# Moty_Light.net
KiCad netlist of a schematic drawn in EAGLE
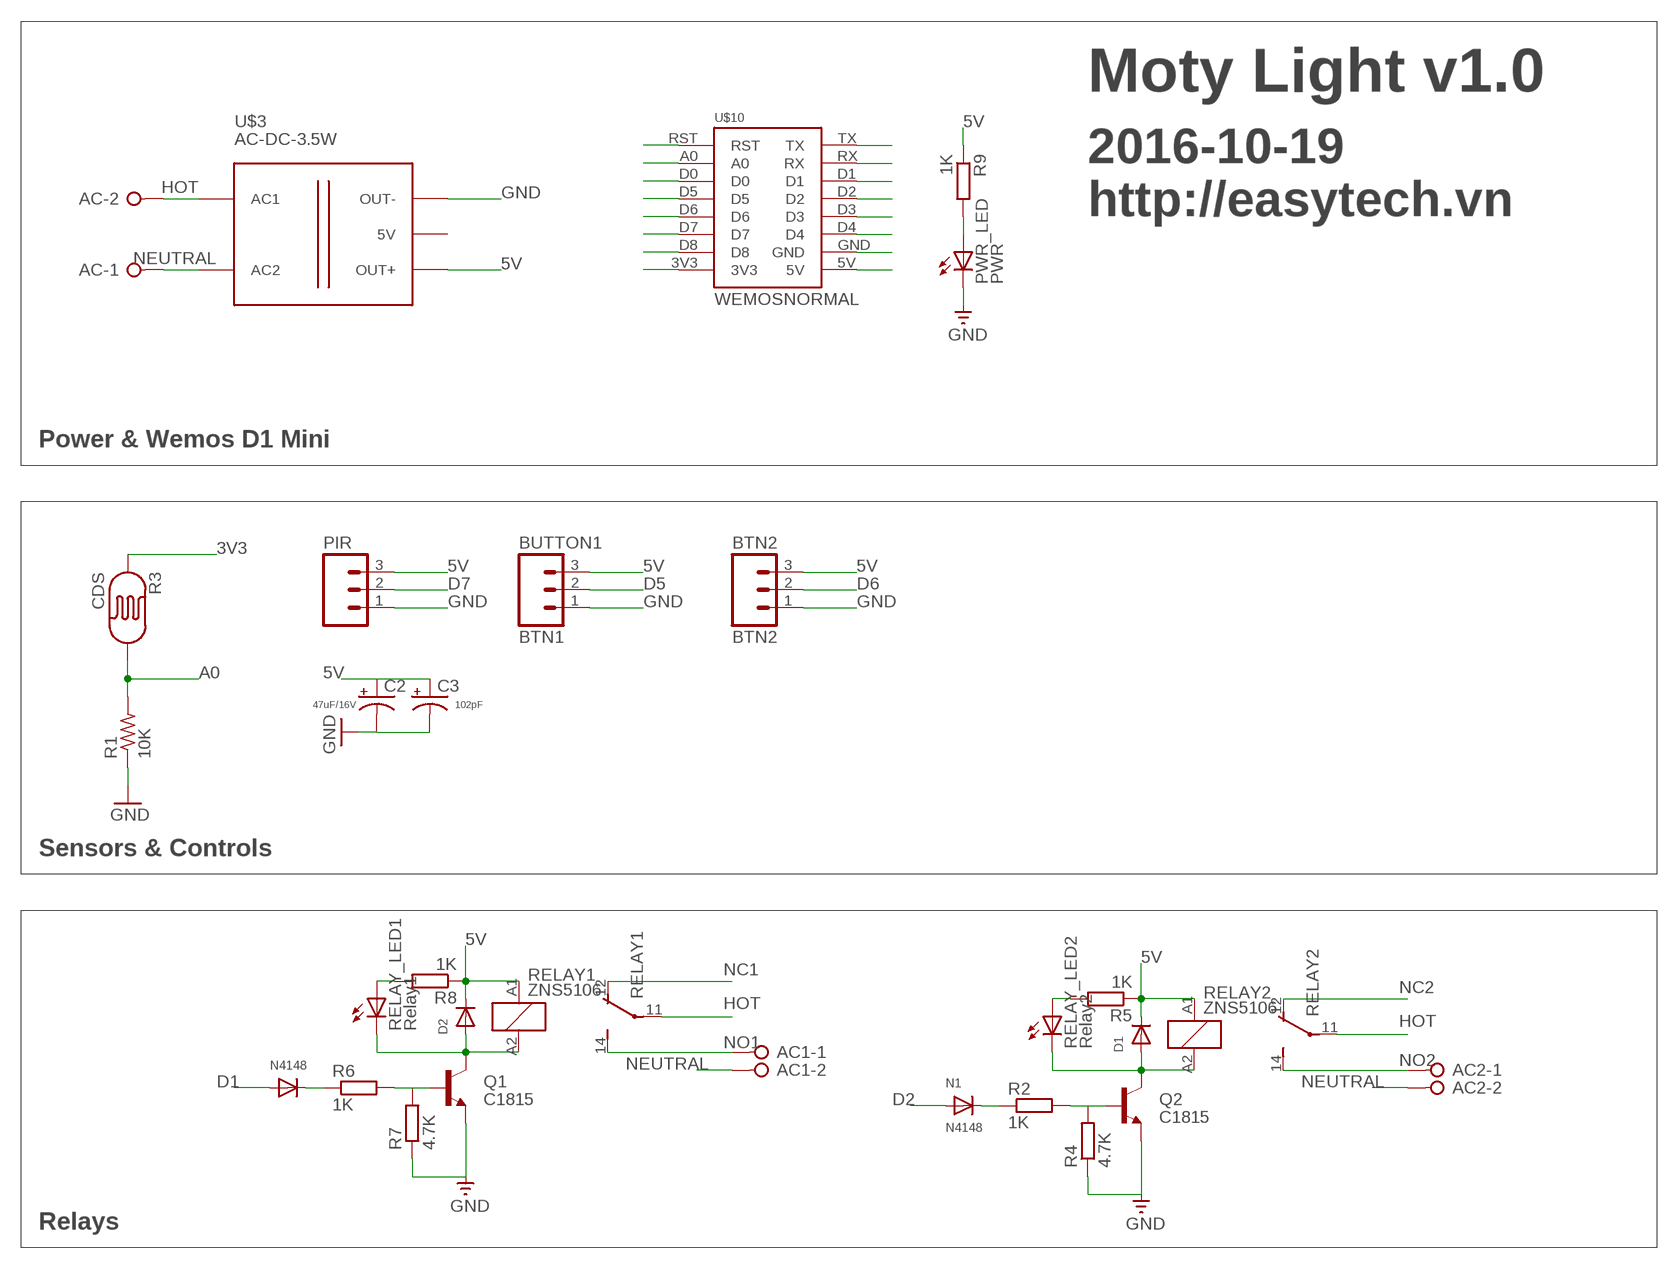
[diagram p0: schematic, sheet 1]

(export (version "E")
  (design (tool "Eeschema 10.0.6"))
  (components
    (comp (ref "AC")
      (value "W237-02P")
      (footprint "eagle-import:W237-132")
      (libsource (lib "eagle-import") (part "W237-02P"))
    )
    (comp (ref "AC1")
      (value "W237-02P")
      (footprint "eagle-import:W237-132")
      (libsource (lib "eagle-import") (part "W237-02P"))
    )
    (comp (ref "AC2")
      (value "W237-02P")
      (footprint "eagle-import:W237-132")
      (libsource (lib "eagle-import") (part "W237-02P"))
    )
    (comp (ref "BTN2")
      (value "BTN2")
      (footprint "eagle-import:1X03")
      (libsource (lib "eagle-import") (part "M03PTH"))
    )
    (comp (ref "BUTTON1")
      (value "BTN1")
      (footprint "eagle-import:1X03")
      (libsource (lib "eagle-import") (part "M03PTH"))
    )
    (comp (ref "C2")
      (value "47uF/16V")
      (footprint "eagle-import:CPOL-RADIAL-10UF-25V")
      (libsource (lib "eagle-import") (part "CAP_POLPTH2"))
    )
    (comp (ref "C3")
      (value "102pF")
      (footprint "eagle-import:CPOL-RADIAL-10UF-25V")
      (libsource (lib "eagle-import") (part "CAP_POLPTH2"))
    )
    (comp (ref "D1")
      (value "DIODESMA")
      (footprint "eagle-import:SMADIODE")
      (libsource (lib "eagle-import") (part "DIODESMA"))
    )
    (comp (ref "D2")
      (value "DIODESMA")
      (footprint "eagle-import:SMADIODE")
      (libsource (lib "eagle-import") (part "DIODESMA"))
    )
    (comp (ref "N1")
      (value "N4148")
      (footprint "eagle-import:SOD-123")
      (libsource (lib "eagle-import") (part "DIODESOD-123"))
    )
    (comp (ref "N4148")
      (value "DIODESOD-123")
      (footprint "eagle-import:SOD-123")
      (libsource (lib "eagle-import") (part "DIODESOD-123"))
    )
    (comp (ref "PIR")
      (value "M03PTH")
      (footprint "eagle-import:1X03")
      (libsource (lib "eagle-import") (part "M03PTH"))
    )
    (comp (ref "PWR_LED")
      (value "PWR")
      (footprint "eagle-import:LED3MM")
      (libsource (lib "eagle-import") (part "LED3MM"))
    )
    (comp (ref "Q1")
      (value "C1815")
      (footprint "eagle-import:SOT23-3")
      (libsource (lib "eagle-import") (part "TRANSISTOR_NPNSOT23-3"))
    )
    (comp (ref "Q2")
      (value "C1815")
      (footprint "eagle-import:SOT23-3")
      (libsource (lib "eagle-import") (part "TRANSISTOR_NPNSOT23-3"))
    )
    (comp (ref "R1")
      (value "10K")
      (footprint "eagle-import:R0805")
      (libsource (lib "eagle-import") (part "R-US_R0805"))
    )
    (comp (ref "R2")
      (value "1K")
      (footprint "eagle-import:R0805")
      (libsource (lib "eagle-import") (part "R-EU_R0805"))
    )
    (comp (ref "R3")
      (value "CDS")
      (footprint "eagle-import:PHOTOCELL_THIN")
      (libsource (lib "eagle-import") (part "PHOTOCELL"))
    )
    (comp (ref "R4")
      (value "4.7K")
      (footprint "eagle-import:R0805")
      (libsource (lib "eagle-import") (part "R-EU_R0805"))
    )
    (comp (ref "R5")
      (value "1K")
      (footprint "eagle-import:R0805")
      (libsource (lib "eagle-import") (part "R-EU_R0805"))
    )
    (comp (ref "R6")
      (value "1K")
      (footprint "eagle-import:R0805")
      (libsource (lib "eagle-import") (part "R-EU_R0805"))
    )
    (comp (ref "R7")
      (value "4.7K")
      (footprint "eagle-import:R0805")
      (libsource (lib "eagle-import") (part "R-EU_R0805"))
    )
    (comp (ref "R8")
      (value "1K")
      (footprint "eagle-import:R0805")
      (libsource (lib "eagle-import") (part "R-EU_R0805"))
    )
    (comp (ref "R9")
      (value "1K")
      (footprint "eagle-import:R0805")
      (libsource (lib "eagle-import") (part "R-EU_R0805"))
    )
    (comp (ref "RELAY1")
      (value "ZNS5106")
      (footprint "eagle-import:ZN5")
      (libsource (lib "eagle-import") (part "ZNS5106"))
    )
    (comp (ref "RELAY2")
      (value "ZNS5106")
      (footprint "eagle-import:ZN5")
      (libsource (lib "eagle-import") (part "ZNS5106"))
    )
    (comp (ref "RELAY_LED1")
      (value "Relay1")
      (footprint "eagle-import:LED3MM")
      (libsource (lib "eagle-import") (part "LED3MM"))
    )
    (comp (ref "RELAY_LED2")
      (value "Relay2")
      (footprint "eagle-import:LED3MM")
      (libsource (lib "eagle-import") (part "LED3MM"))
    )
    (comp (ref "U$3")
      (value "AC-DC-3.5W")
      (footprint "eagle-import:AC-DC-3.5W")
      (libsource (lib "eagle-import") (part "AC-DC-3.5W"))
    )
    (comp (ref "U$10")
      (value "WEMOSNORMAL")
      (footprint "eagle-import:WEMOS")
      (libsource (lib "eagle-import") (part "WEMOSNORMAL"))
    )
  )
  (nets
    (net (code "1") (name "/3V3") (class "Default")
      (node (ref "R3") (pin "1") (pinfunction "P$1_1") (pintype "bidirectional"))
      (node (ref "U$10") (pin "3V3") (pinfunction "3V3_3V3") (pintype "bidirectional"))
    )
    (net (code "2") (name "/5V") (class "Default")
      (node (ref "BTN2") (pin "3") (pinfunction "3_3") (pintype "passive"))
      (node (ref "BUTTON1") (pin "3") (pinfunction "3_3") (pintype "passive"))
      (node (ref "C2") (pin "1") (pinfunction "+_1") (pintype "passive"))
      (node (ref "C3") (pin "1") (pinfunction "+_1") (pintype "passive"))
      (node (ref "D1") (pin "C") (pinfunction "C_C") (pintype "passive"))
      (node (ref "D2") (pin "C") (pinfunction "C_C") (pintype "passive"))
      (node (ref "PIR") (pin "3") (pinfunction "3_3") (pintype "passive"))
      (node (ref "R5") (pin "1") (pinfunction "1_1") (pintype "passive"))
      (node (ref "R8") (pin "1") (pinfunction "1_1") (pintype "passive"))
      (node (ref "R9") (pin "1") (pinfunction "1_1") (pintype "passive"))
      (node (ref "RELAY1") (pin "A1") (pinfunction "1_A1") (pintype "passive"))
      (node (ref "RELAY2") (pin "A1") (pinfunction "1_A1") (pintype "passive"))
      (node (ref "U$10") (pin "5V") (pinfunction "5V_5V") (pintype "bidirectional"))
      (node (ref "U$3") (pin "J2.3") (pinfunction "OUT+_J2.3") (pintype "bidirectional"))
    )
    (net (code "3") (name "/A0") (class "Default")
      (node (ref "R1") (pin "2") (pinfunction "2_2") (pintype "passive"))
      (node (ref "R3") (pin "2") (pinfunction "P$2_2") (pintype "bidirectional"))
      (node (ref "U$10") (pin "A0") (pinfunction "A0_A0") (pintype "bidirectional"))
    )
    (net (code "4") (name "/D1") (class "Default")
      (node (ref "N4148") (pin "A") (pinfunction "A_A") (pintype "passive"))
      (node (ref "U$10") (pin "D1") (pinfunction "D1_D1") (pintype "bidirectional"))
    )
    (net (code "5") (name "/D2") (class "Default")
      (node (ref "N1") (pin "A") (pinfunction "A_A") (pintype "passive"))
      (node (ref "U$10") (pin "D2") (pinfunction "D2_D2") (pintype "bidirectional"))
    )
    (net (code "6") (name "/D5") (class "Default")
      (node (ref "BUTTON1") (pin "2") (pinfunction "2_2") (pintype "passive"))
      (node (ref "U$10") (pin "D5") (pinfunction "D5_D5") (pintype "bidirectional"))
    )
    (net (code "7") (name "/D6") (class "Default")
      (node (ref "BTN2") (pin "2") (pinfunction "2_2") (pintype "passive"))
      (node (ref "U$10") (pin "D6") (pinfunction "D6_D6") (pintype "bidirectional"))
    )
    (net (code "8") (name "/D7") (class "Default")
      (node (ref "PIR") (pin "2") (pinfunction "2_2") (pintype "passive"))
      (node (ref "U$10") (pin "D7") (pinfunction "D7_D7") (pintype "bidirectional"))
    )
    (net (code "9") (name "/HOT") (class "Default")
      (node (ref "AC") (pin "2") (pinfunction "KL_2") (pintype "passive"))
      (node (ref "RELAY1") (pin "11") (pinfunction "P_11") (pintype "passive"))
      (node (ref "RELAY2") (pin "11") (pinfunction "P_11") (pintype "passive"))
      (node (ref "U$3") (pin "J1.1") (pinfunction "AC1_J1.1") (pintype "bidirectional"))
    )
    (net (code "10") (name "/NC1") (class "Default")
      (node (ref "RELAY1") (pin "12") (pinfunction "O_12") (pintype "passive"))
    )
    (net (code "11") (name "/NC2") (class "Default")
      (node (ref "RELAY2") (pin "12") (pinfunction "O_12") (pintype "passive"))
    )
    (net (code "12") (name "/NEUTRAL") (class "Default")
      (node (ref "AC") (pin "1") (pinfunction "KL_1") (pintype "passive"))
      (node (ref "AC1") (pin "2") (pinfunction "KL_2") (pintype "passive"))
      (node (ref "AC2") (pin "2") (pinfunction "KL_2") (pintype "passive"))
      (node (ref "U$3") (pin "J1.2") (pinfunction "AC2_J1.2") (pintype "bidirectional"))
    )
    (net (code "13") (name "/NO1") (class "Default")
      (node (ref "AC1") (pin "1") (pinfunction "KL_1") (pintype "passive"))
      (node (ref "RELAY1") (pin "14") (pinfunction "S_14") (pintype "passive"))
    )
    (net (code "14") (name "/NO2") (class "Default")
      (node (ref "AC2") (pin "1") (pinfunction "KL_1") (pintype "passive"))
      (node (ref "RELAY2") (pin "14") (pinfunction "S_14") (pintype "passive"))
    )
    (net (code "15") (name "GND") (class "Default")
      (node (ref "BTN2") (pin "1") (pinfunction "1_1") (pintype "passive"))
      (node (ref "BUTTON1") (pin "1") (pinfunction "1_1") (pintype "passive"))
      (node (ref "C2") (pin "2") (pinfunction "-_2") (pintype "passive"))
      (node (ref "C3") (pin "2") (pinfunction "-_2") (pintype "passive"))
      (node (ref "PIR") (pin "1") (pinfunction "1_1") (pintype "passive"))
      (node (ref "PWR_LED") (pin "K") (pinfunction "C_K") (pintype "passive"))
      (node (ref "Q1") (pin "2") (pinfunction "E_2") (pintype "passive"))
      (node (ref "Q2") (pin "2") (pinfunction "E_2") (pintype "passive"))
      (node (ref "R1") (pin "1") (pinfunction "1_1") (pintype "passive"))
      (node (ref "R4") (pin "1") (pinfunction "1_1") (pintype "passive"))
      (node (ref "R7") (pin "1") (pinfunction "1_1") (pintype "passive"))
      (node (ref "U$10") (pin "GND") (pinfunction "GND_GND") (pintype "bidirectional"))
      (node (ref "U$3") (pin "J2.1") (pinfunction "OUT-_J2.1") (pintype "bidirectional"))
    )
    (net (code "16") (name "Net-(N1-PadC)") (class "Default")
      (node (ref "N1") (pin "C") (pinfunction "C_C") (pintype "passive"))
      (node (ref "R2") (pin "1") (pinfunction "1_1") (pintype "passive"))
    )
    (net (code "17") (name "Net-(N4148-PadC)") (class "Default")
      (node (ref "N4148") (pin "C") (pinfunction "C_C") (pintype "passive"))
      (node (ref "R6") (pin "1") (pinfunction "1_1") (pintype "passive"))
    )
    (net (code "18") (name "Net-(PWR_LED-PadA)") (class "Default")
      (node (ref "PWR_LED") (pin "A") (pinfunction "A_A") (pintype "passive"))
      (node (ref "R9") (pin "2") (pinfunction "2_2") (pintype "passive"))
    )
    (net (code "19") (name "Net-(Q1-B)") (class "Default")
      (node (ref "Q1") (pin "1") (pinfunction "B_1") (pintype "passive"))
      (node (ref "R6") (pin "2") (pinfunction "2_2") (pintype "passive"))
      (node (ref "R7") (pin "2") (pinfunction "2_2") (pintype "passive"))
    )
    (net (code "20") (name "Net-(Q1-C)") (class "Default")
      (node (ref "D2") (pin "A") (pinfunction "A_A") (pintype "passive"))
      (node (ref "Q1") (pin "3") (pinfunction "C_3") (pintype "passive"))
      (node (ref "RELAY1") (pin "A2") (pinfunction "2_A2") (pintype "passive"))
      (node (ref "RELAY_LED1") (pin "K") (pinfunction "C_K") (pintype "passive"))
    )
    (net (code "21") (name "Net-(Q2-B)") (class "Default")
      (node (ref "Q2") (pin "1") (pinfunction "B_1") (pintype "passive"))
      (node (ref "R2") (pin "2") (pinfunction "2_2") (pintype "passive"))
      (node (ref "R4") (pin "2") (pinfunction "2_2") (pintype "passive"))
    )
    (net (code "22") (name "Net-(Q2-C)") (class "Default")
      (node (ref "D1") (pin "A") (pinfunction "A_A") (pintype "passive"))
      (node (ref "Q2") (pin "3") (pinfunction "C_3") (pintype "passive"))
      (node (ref "RELAY2") (pin "A2") (pinfunction "2_A2") (pintype "passive"))
      (node (ref "RELAY_LED2") (pin "K") (pinfunction "C_K") (pintype "passive"))
    )
    (net (code "23") (name "Net-(R5-Pad2)") (class "Default")
      (node (ref "R5") (pin "2") (pinfunction "2_2") (pintype "passive"))
      (node (ref "RELAY_LED2") (pin "A") (pinfunction "A_A") (pintype "passive"))
    )
    (net (code "24") (name "Net-(R8-Pad2)") (class "Default")
      (node (ref "R8") (pin "2") (pinfunction "2_2") (pintype "passive"))
      (node (ref "RELAY_LED1") (pin "A") (pinfunction "A_A") (pintype "passive"))
    )
    (net (code "25") (name "unconnected-(U$3-5V-PadJ2.2)") (class "Default")
      (node (ref "U$3") (pin "J2.2") (pinfunction "5V_J2.2") (pintype "bidirectional"))
    )
    (net (code "26") (name "unconnected-(U$10-PadD0)") (class "Default")
      (node (ref "U$10") (pin "D0") (pinfunction "D0_D0") (pintype "bidirectional"))
    )
    (net (code "27") (name "unconnected-(U$10-PadD3)") (class "Default")
      (node (ref "U$10") (pin "D3") (pinfunction "D3_D3") (pintype "bidirectional"))
    )
    (net (code "28") (name "unconnected-(U$10-PadD4)") (class "Default")
      (node (ref "U$10") (pin "D4") (pinfunction "D4_D4") (pintype "bidirectional"))
    )
    (net (code "29") (name "unconnected-(U$10-PadD8)") (class "Default")
      (node (ref "U$10") (pin "D8") (pinfunction "D8_D8") (pintype "bidirectional"))
    )
    (net (code "30") (name "unconnected-(U$10-PadRST)") (class "Default")
      (node (ref "U$10") (pin "RST") (pinfunction "RST_RST") (pintype "bidirectional"))
    )
    (net (code "31") (name "unconnected-(U$10-PadRX)") (class "Default")
      (node (ref "U$10") (pin "RX") (pinfunction "RX_RX") (pintype "bidirectional"))
    )
    (net (code "32") (name "unconnected-(U$10-PadTX)") (class "Default")
      (node (ref "U$10") (pin "TX") (pinfunction "TX_TX") (pintype "bidirectional"))
    )
  )
)
